# Differentiator.net
KiCad netlist of a schematic drawn in Altium Designer
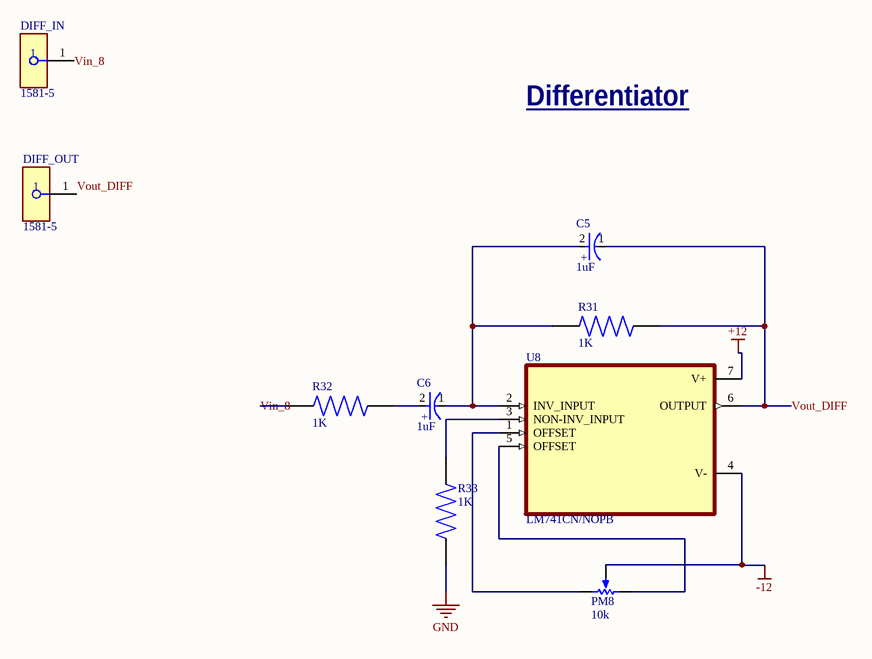
[diagram p0: Differentiator.SchDoc]

(export (version "E")
  (design (tool "Eeschema 10.0.6"))
  (components
    (comp (ref "C5")
      (value "1uF")
      (footprint "FP-ECA-2CHG010I-MFG")
      (description "CAP ALUM 1UF 20% 160V RADIAL")
      (fields (field (name "TOLERANCE") "20%"))
      (libsource (lib "Altium Content Vault") (part "a00bbbee19879c290e62620ae7e47b1"))
    )
    (comp (ref "C6")
      (value "1uF")
      (footprint "FP-ECA-2CHG010I-MFG")
      (description "CAP ALUM 1UF 20% 160V RADIAL")
      (fields (field (name "TOLERANCE") "20%"))
      (libsource (lib "Altium Content Vault") (part "a00bbbee19879c290e62620ae7e47b1"))
    )
    (comp (ref "DIFF_IN")
      (value "1581-5")
      (footprint "FP-1581-5-MFG")
      (description "CONN BANANA JACK TURRET GREEN")
      (libsource (lib "Altium Content Vault") (part "c5c826e0c4b67fe3b42ef77f2d4decc"))
    )
    (comp (ref "DIFF_OUT")
      (value "1581-5")
      (footprint "FP-1581-5-MFG")
      (description "CONN BANANA JACK TURRET GREEN")
      (libsource (lib "Altium Content Vault") (part "c5c826e0c4b67fe3b42ef77f2d4decc"))
    )
    (comp (ref "PM8")
      (value "10k")
      (footprint "BOUR-3362P")
      (description "Square Trimpot(R) Trimming Potentiometer, 10 KOhm, 300 V, -55 to 125 degC, 3-Pin THD, RoHS, Tube")
      (fields (field (name "TOLERANCE") "1%"))
      (libsource (lib "Altium Content Vault") (part "RES-POT-3"))
    )
    (comp (ref "R31")
      (value "1K")
      (footprint "RESAD1100W55L680D260")
      (description "1.07 kOhms Â±1% 0.25W, 1/4W Through Hole Resistor Axial - Metal Film")
      (fields (field (name "MF") "Yageo") (field (name "MP") "MFR-25FBF52-1K"))
      (libsource (lib "MFR-25FBF52-1K") (part "MFR-25FBF52-1K"))
    )
    (comp (ref "R32")
      (value "1K")
      (footprint "RESAD1100W55L680D260")
      (description "1.07 kOhms Â±1% 0.25W, 1/4W Through Hole Resistor Axial - Metal Film")
      (fields (field (name "MF") "Yageo") (field (name "MP") "MFR-25FBF52-1K"))
      (libsource (lib "MFR-25FBF52-1K") (part "MFR-25FBF52-1K"))
    )
    (comp (ref "R33")
      (value "1K")
      (footprint "RESAD1100W55L680D260")
      (description "1.07 kOhms Â±1% 0.25W, 1/4W Through Hole Resistor Axial - Metal Film")
      (fields (field (name "MF") "Yageo") (field (name "MP") "MFR-25FBF52-1K"))
      (libsource (lib "MFR-25FBF52-1K") (part "MFR-25FBF52-1K"))
    )
    (comp (ref "U8")
      (value "LM741CN/NOPB")
      (footprint "DIP794W45P254L959H508Q8")
      (description "Single, 44-V, 1-MHz operational amplifier")
      (fields (field (name "MF") "Texas Instruments"))
      (libsource (lib "LM741CN_NOPB (1)") (part "LM741CN/NOPB"))
    )
  )
  (nets
    (net (code "1") (name "+12") (class "Default")
      (node (ref "U8") (pin "7") (pinfunction "V+_7") (pintype "power_in"))
    )
    (net (code "2") (name "-12") (class "Default")
      (node (ref "PM8") (pin "2") (pinfunction "S_2") (pintype "passive"))
      (node (ref "U8") (pin "4") (pinfunction "V-_4") (pintype "power_in"))
    )
    (net (code "3") (name "/Vin_8") (class "Default")
      (node (ref "DIFF_IN") (pin "1") (pinfunction "1_1") (pintype "passive"))
      (node (ref "R32") (pin "1") (pinfunction "1_1") (pintype "passive"))
    )
    (net (code "4") (name "/Vout_DIFF") (class "Default")
      (node (ref "C5") (pin "1") (pinfunction "C_1") (pintype "passive"))
      (node (ref "DIFF_OUT") (pin "1") (pinfunction "1_1") (pintype "passive"))
      (node (ref "R31") (pin "2") (pinfunction "2_2") (pintype "passive"))
      (node (ref "U8") (pin "6") (pinfunction "OUTPUT_6") (pintype "output"))
    )
    (net (code "5") (name "GND") (class "Default")
      (node (ref "R33") (pin "1") (pinfunction "1_1") (pintype "passive"))
    )
    (net (code "6") (name "Net-(C5-A)") (class "Default")
      (node (ref "C5") (pin "2") (pinfunction "A_2") (pintype "passive"))
      (node (ref "C6") (pin "1") (pinfunction "C_1") (pintype "passive"))
      (node (ref "R31") (pin "1") (pinfunction "1_1") (pintype "passive"))
      (node (ref "U8") (pin "2") (pinfunction "INV_INPUT_2") (pintype "input"))
    )
    (net (code "7") (name "Net-(C6-A)") (class "Default")
      (node (ref "C6") (pin "2") (pinfunction "A_2") (pintype "passive"))
      (node (ref "R32") (pin "2") (pinfunction "2_2") (pintype "passive"))
    )
    (net (code "8") (name "Net-(PM8-CCW)") (class "Default")
      (node (ref "PM8") (pin "1") (pinfunction "CCW_1") (pintype "passive"))
      (node (ref "U8") (pin "5") (pinfunction "OFFSET_5") (pintype "input"))
    )
    (net (code "9") (name "Net-(PM8-CW)") (class "Default")
      (node (ref "PM8") (pin "3") (pinfunction "CW_3") (pintype "passive"))
      (node (ref "U8") (pin "1") (pinfunction "OFFSET_1") (pintype "input"))
    )
    (net (code "10") (name "Net-(U8-NON-INV_INPUT)") (class "Default")
      (node (ref "R33") (pin "2") (pinfunction "2_2") (pintype "passive"))
      (node (ref "U8") (pin "3") (pinfunction "NON-INV_INPUT_3") (pintype "input"))
    )
  )
)
